# MPPT_CC_CV_charger.net
KiCad netlist of a schematic drawn in Altium Designer
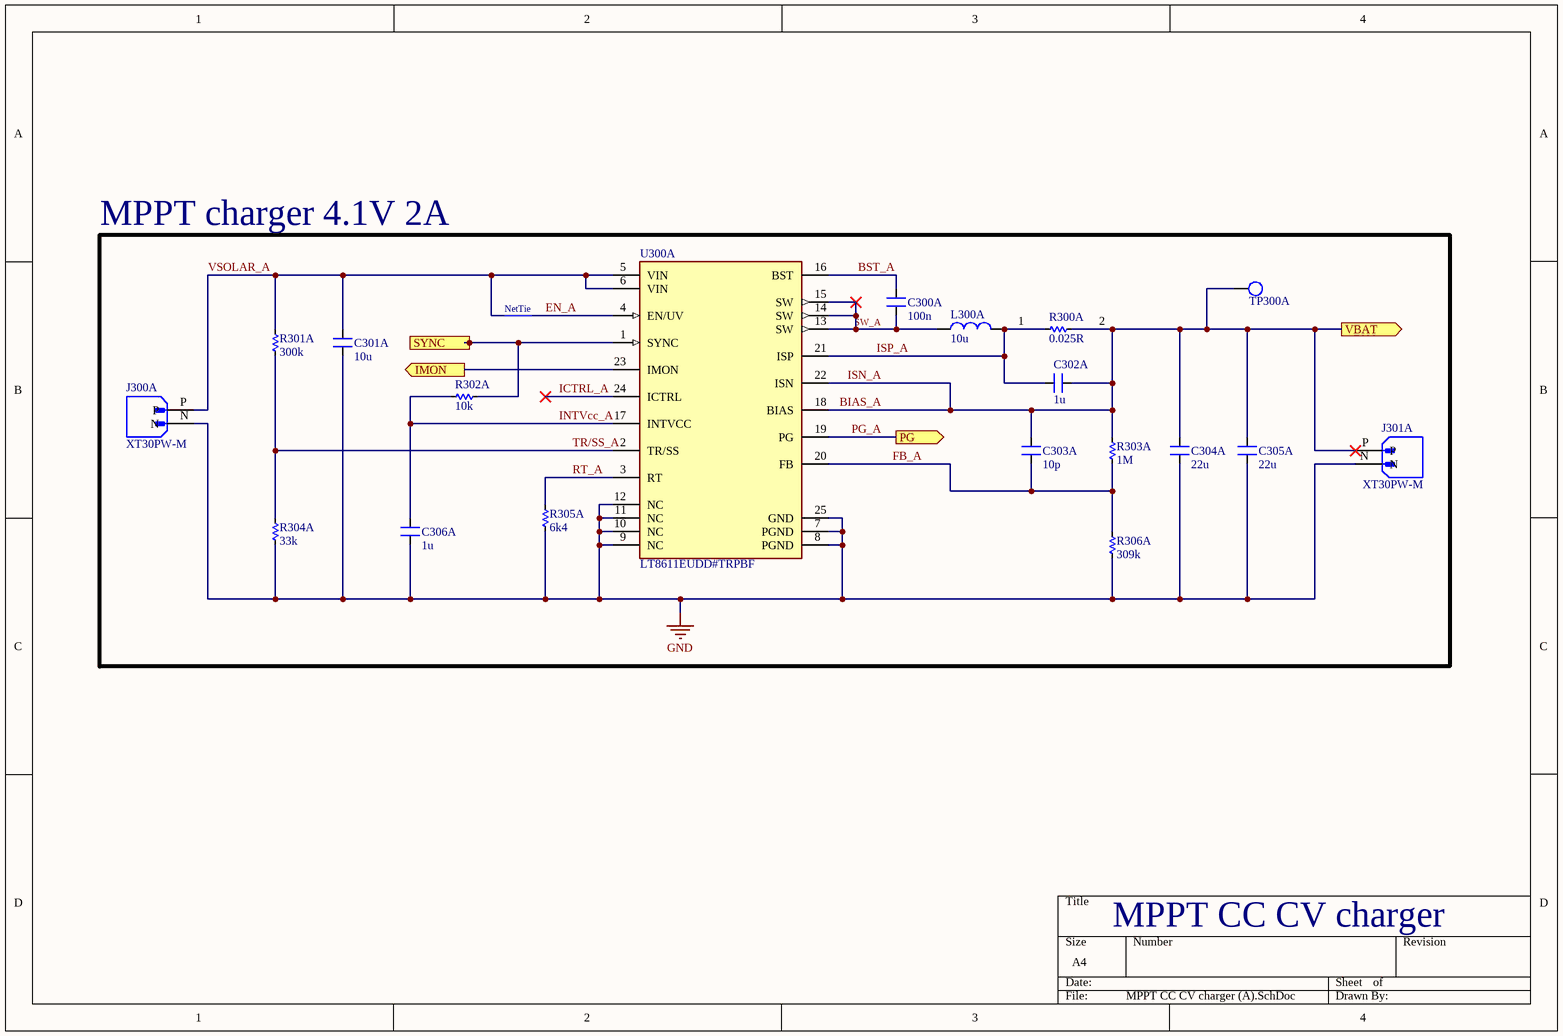
[diagram p0: MPPT CC CV charger (A).SchDoc]

(export (version "E")
  (design (tool "Eeschema 10.0.6"))
  (components
    (comp (ref "C300A") (value "100n") (footprint "CN-SMD-0603") (libsource (lib "Library") (part "CN")))
    (comp (ref "C301A") (value "10u") (footprint "CN-SMD-0603") (libsource (lib "Library") (part "CN")))
    (comp (ref "C302A") (value "1u") (footprint "CN-SMD-0603") (libsource (lib "Library") (part "CN")))
    (comp (ref "C303A") (value "10p") (footprint "CN-SMD-0603") (libsource (lib "Library") (part "CN")))
    (comp (ref "C304A") (value "22u") (footprint "CN-SMD-0603") (libsource (lib "Library") (part "CN")))
    (comp (ref "C305A") (value "22u") (footprint "CN-SMD-0603") (libsource (lib "Library") (part "CN")))
    (comp (ref "C306A") (value "1u") (footprint "CN-SMD-0603") (libsource (lib "Library") (part "CN")))
    (comp (ref "J300A")
      (value "XT30PW-M")
      (footprint "AMASS_XT30PW-M")
      (description "Socket; DC supply; XT30; male; PIN: 2; on PCBs; THT; Colour: yellow")
      (fields (field (name "MF") "AMASS"))
      (libsource (lib "") (part "XT30PW-M_1"))
    )
    (comp (ref "J301A")
      (value "XT30PW-M")
      (footprint "AMASS_XT30PW-M")
      (description "Socket; DC supply; XT30; male; PIN: 2; on PCBs; THT; Colour: yellow")
      (fields (field (name "MF") "AMASS"))
      (libsource (lib "XT30PW-M") (part "XT30PW-M"))
    )
    (comp (ref "L300A")
      (value "10u")
      (footprint "L-SMD-M-7.3x4.5")
      (fields
        (field (name "PARTNO") "78477010")
        (field (name "MANUFACTURER") "Wurth Elektronik")
        (field (name "CREATED BY") "Baojun Chen")
      )
      (libsource (lib "Library") (part "L-SMD-1"))
    )
    (comp (ref "R300A")
      (value "0.025R")
      (footprint "RES-SMD-0603")
      (description "Resistor")
      (fields
        (field (name "MANUFACTURER") "Generic Components")
        (field (name "PUBLISHER") "Altium Hobart Technology Centre")
      )
      (libsource (lib "Library") (part "Res-SMD"))
    )
    (comp (ref "R301A")
      (value "300k")
      (footprint "RES-SMD-0603")
      (description "Resistor")
      (fields
        (field (name "MANUFACTURER") "Generic Components")
        (field (name "PUBLISHER") "Altium Hobart Technology Centre")
      )
      (libsource (lib "Library") (part "Res-SMD"))
    )
    (comp (ref "R302A")
      (value "10k")
      (footprint "RES-SMD-0603")
      (description "Resistor")
      (fields
        (field (name "MANUFACTURER") "Generic Components")
        (field (name "PUBLISHER") "Altium Hobart Technology Centre")
      )
      (libsource (lib "Library") (part "Res-SMD"))
    )
    (comp (ref "R303A")
      (value "1M")
      (footprint "RES-SMD-0603")
      (description "Resistor")
      (fields
        (field (name "MANUFACTURER") "Generic Components")
        (field (name "PUBLISHER") "Altium Hobart Technology Centre")
      )
      (libsource (lib "Library") (part "Res-SMD"))
    )
    (comp (ref "R304A")
      (value "33k")
      (footprint "RES-SMD-0603")
      (description "Resistor")
      (fields
        (field (name "MANUFACTURER") "Generic Components")
        (field (name "PUBLISHER") "Altium Hobart Technology Centre")
      )
      (libsource (lib "Library") (part "Res-SMD"))
    )
    (comp (ref "R305A")
      (value "6k4")
      (footprint "RES-SMD-0603")
      (description "Resistor")
      (fields
        (field (name "MANUFACTURER") "Generic Components")
        (field (name "PUBLISHER") "Altium Hobart Technology Centre")
      )
      (libsource (lib "Library") (part "Res-SMD"))
    )
    (comp (ref "R306A")
      (value "309k")
      (footprint "RES-SMD-0603")
      (description "Resistor")
      (fields
        (field (name "MANUFACTURER") "Generic Components")
        (field (name "PUBLISHER") "Altium Hobart Technology Centre")
      )
      (libsource (lib "Library") (part "Res-SMD"))
    )
    (comp (ref "TP300A")
      (value "Test-Point")
      (footprint "TESTPOINT")
      (libsource (lib "Library") (part "Test-Point"))
    )
    (comp (ref "U300A")
      (value "LT8611EUDD#TRPBF")
      (footprint "FP-UDD-24-05-08-1833-IPC_B")
      (description "IC REG BUCK ADJ 2.5A 24QFN")
      (libsource (lib "Altium Content Vault") (part "fa917c90ce6974f84498b26f3756de5"))
    )
  )
  (nets
    (net (code "1") (name "/BIAS_A") (class "Default")
      (node (ref "C302A") (pin "2") (pinfunction "2_2") (pintype "passive"))
      (node (ref "C303A") (pin "2") (pinfunction "2_2") (pintype "passive"))
      (node (ref "C304A") (pin "2") (pinfunction "2_2") (pintype "passive"))
      (node (ref "C305A") (pin "2") (pinfunction "2_2") (pintype "passive"))
      (node (ref "J301A") (pin "P") (pinfunction "P_P") (pintype "power_in"))
      (node (ref "R300A") (pin "1") (pinfunction "1_1") (pintype "passive"))
      (node (ref "R303A") (pin "1") (pinfunction "1_1") (pintype "passive"))
      (node (ref "TP300A") (pin "1") (pinfunction "1_1") (pintype "passive"))
      (node (ref "U300A") (pin "18") (pinfunction "BIAS_18") (pintype "passive"))
      (node (ref "U300A") (pin "22") (pinfunction "ISN_22") (pintype "passive"))
    )
    (net (code "2") (name "/BST_A") (class "Default")
      (node (ref "C300A") (pin "2") (pinfunction "2_2") (pintype "passive"))
      (node (ref "U300A") (pin "16") (pinfunction "BST_16") (pintype "passive"))
    )
    (net (code "3") (name "/EN_A") (class "Default")
      (node (ref "C301A") (pin "2") (pinfunction "2_2") (pintype "passive"))
      (node (ref "J300A") (pin "P") (pinfunction "P_P") (pintype "power_in"))
      (node (ref "R301A") (pin "2") (pinfunction "2_2") (pintype "passive"))
      (node (ref "U300A") (pin "4") (pinfunction "EN/UV_4") (pintype "input"))
      (node (ref "U300A") (pin "5") (pinfunction "VIN_5") (pintype "power_in"))
      (node (ref "U300A") (pin "6") (pinfunction "VIN_6") (pintype "power_in"))
    )
    (net (code "4") (name "/FB_A") (class "Default")
      (node (ref "C303A") (pin "1") (pinfunction "1_1") (pintype "passive"))
      (node (ref "R303A") (pin "2") (pinfunction "2_2") (pintype "passive"))
      (node (ref "R306A") (pin "1") (pinfunction "1_1") (pintype "passive"))
      (node (ref "U300A") (pin "20") (pinfunction "FB_20") (pintype "passive"))
    )
    (net (code "5") (name "/ICTRL_A") (class "Default")
      (node (ref "U300A") (pin "24") (pinfunction "ICTRL_24") (pintype "passive+no_connect"))
    )
    (net (code "6") (name "/IMON") (class "Default")
      (node (ref "U300A") (pin "23") (pinfunction "IMON_23") (pintype "passive"))
    )
    (net (code "7") (name "/INTVcc_A") (class "Default")
      (node (ref "C306A") (pin "2") (pinfunction "2_2") (pintype "passive"))
      (node (ref "R302A") (pin "2") (pinfunction "2_2") (pintype "passive"))
      (node (ref "U300A") (pin "17") (pinfunction "INTVCC_17") (pintype "passive"))
    )
    (net (code "8") (name "/ISP_A") (class "Default")
      (node (ref "C302A") (pin "1") (pinfunction "1_1") (pintype "passive"))
      (node (ref "L300A") (pin "2") (pinfunction "2_2") (pintype "passive"))
      (node (ref "R300A") (pin "2") (pinfunction "2_2") (pintype "passive"))
      (node (ref "U300A") (pin "21") (pinfunction "ISP_21") (pintype "passive"))
    )
    (net (code "9") (name "/PG_A") (class "Default")
      (node (ref "U300A") (pin "19") (pinfunction "PG_19") (pintype "passive"))
    )
    (net (code "10") (name "/RT_A") (class "Default")
      (node (ref "R305A") (pin "2") (pinfunction "2_2") (pintype "passive"))
      (node (ref "U300A") (pin "3") (pinfunction "RT_3") (pintype "passive"))
    )
    (net (code "11") (name "/SW_A") (class "Default")
      (node (ref "C300A") (pin "1") (pinfunction "1_1") (pintype "passive"))
      (node (ref "L300A") (pin "1") (pinfunction "1_1") (pintype "passive"))
      (node (ref "U300A") (pin "13") (pinfunction "SW_13") (pintype "output"))
      (node (ref "U300A") (pin "14") (pinfunction "SW_14") (pintype "output"))
      (node (ref "U300A") (pin "15") (pinfunction "SW_15") (pintype "output"))
    )
    (net (code "12") (name "/SYNC") (class "Default")
      (node (ref "R302A") (pin "1") (pinfunction "1_1") (pintype "passive"))
      (node (ref "U300A") (pin "1") (pinfunction "SYNC_1") (pintype "input"))
    )
    (net (code "13") (name "/TR{slash}SS_A") (class "Default")
      (node (ref "R301A") (pin "1") (pinfunction "1_1") (pintype "passive"))
      (node (ref "R304A") (pin "2") (pinfunction "2_2") (pintype "passive"))
      (node (ref "U300A") (pin "2") (pinfunction "TR/SS_2") (pintype "passive"))
    )
    (net (code "14") (name "GND") (class "Default")
      (node (ref "C301A") (pin "1") (pinfunction "1_1") (pintype "passive"))
      (node (ref "C304A") (pin "1") (pinfunction "1_1") (pintype "passive"))
      (node (ref "C305A") (pin "1") (pinfunction "1_1") (pintype "passive"))
      (node (ref "C306A") (pin "1") (pinfunction "1_1") (pintype "passive"))
      (node (ref "J300A") (pin "N") (pinfunction "N_N") (pintype "power_in"))
      (node (ref "J301A") (pin "N") (pinfunction "N_N") (pintype "power_in"))
      (node (ref "R304A") (pin "1") (pinfunction "1_1") (pintype "passive"))
      (node (ref "R305A") (pin "1") (pinfunction "1_1") (pintype "passive"))
      (node (ref "R306A") (pin "2") (pinfunction "2_2") (pintype "passive"))
      (node (ref "U300A") (pin "10") (pinfunction "NC_10") (pintype "passive"))
      (node (ref "U300A") (pin "11") (pinfunction "NC_11") (pintype "passive"))
      (node (ref "U300A") (pin "12") (pinfunction "NC_12") (pintype "passive"))
      (node (ref "U300A") (pin "25") (pinfunction "GND_25") (pintype "power_in"))
      (node (ref "U300A") (pin "7") (pinfunction "PGND_7") (pintype "power_in"))
      (node (ref "U300A") (pin "8") (pinfunction "PGND_8") (pintype "power_in"))
      (node (ref "U300A") (pin "9") (pinfunction "NC_9") (pintype "passive"))
    )
  )
)
